# driver_f103__EDA.net
KiCad netlist of a schematic drawn in EasyEDA
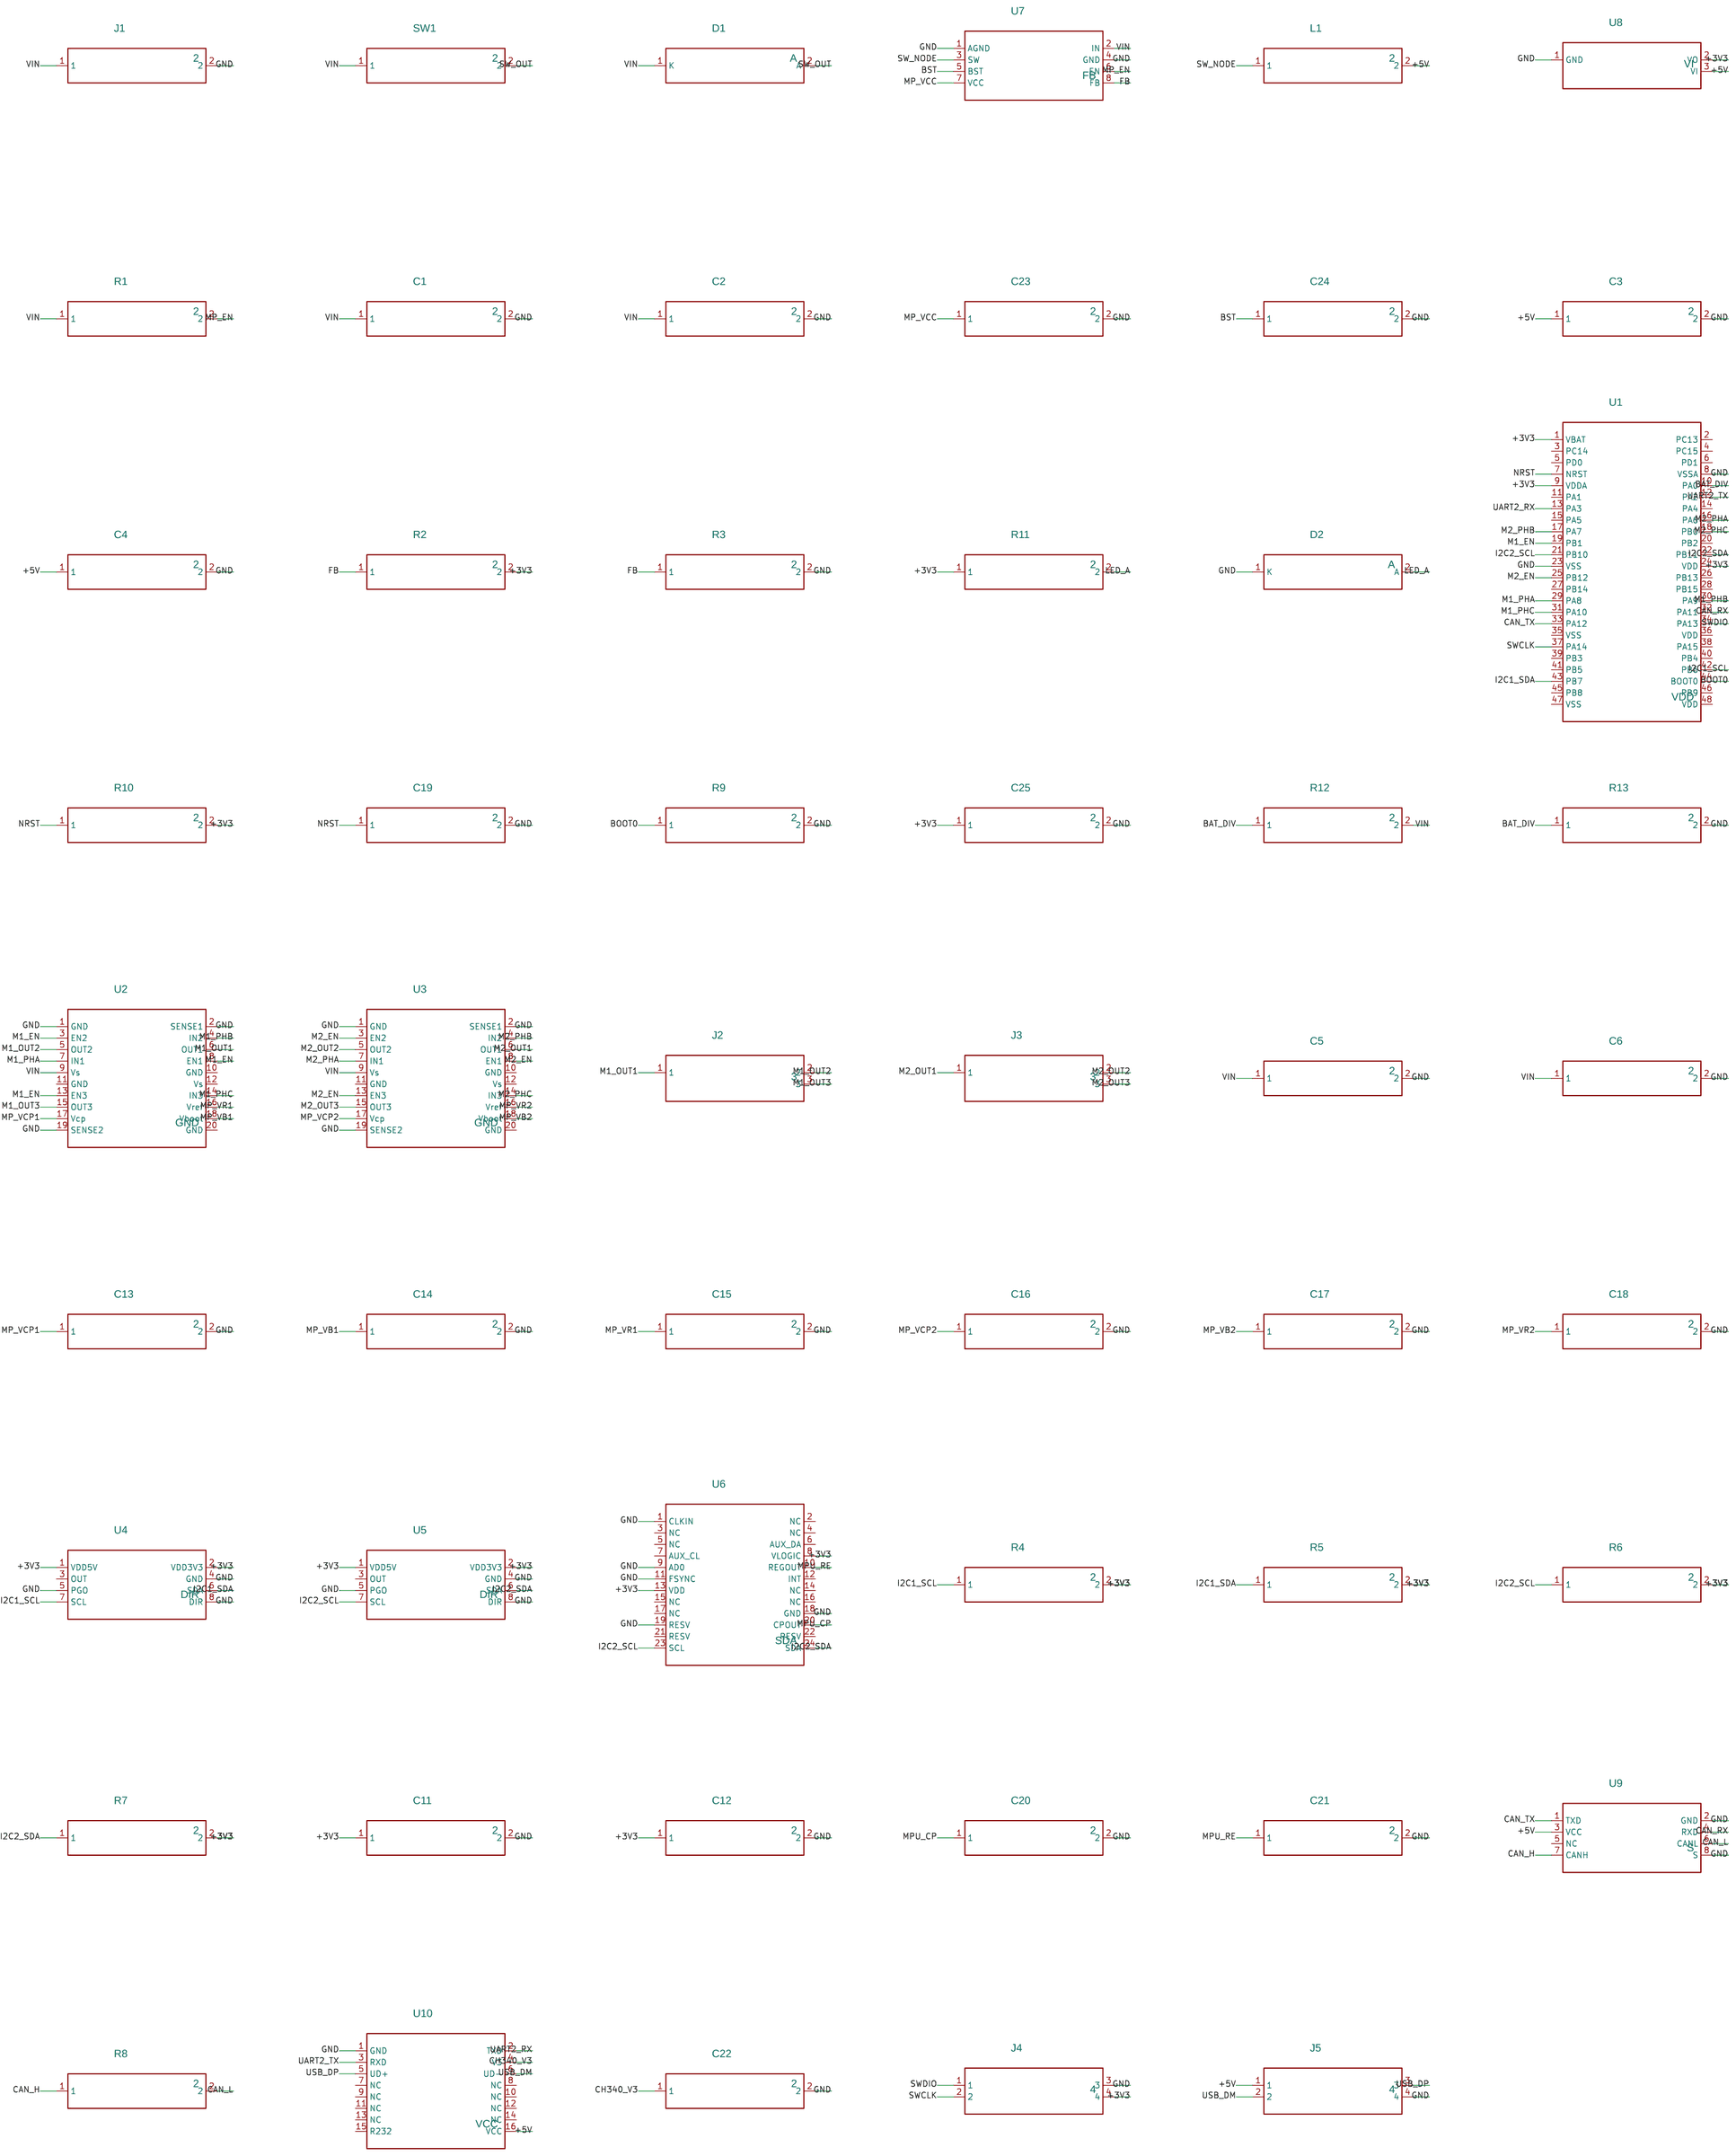
[diagram p0: schematic sheet]

(export (version "E")
  (design (tool "Eeschema 10.0.6"))
  (components
    (comp (ref "C1") (value "22uF") (libsource (lib "") (part "Unknown_560_520")))
    (comp (ref "C2") (value "0.1uF") (libsource (lib "") (part "Unknown_820_520")))
    (comp (ref "C3") (value "22uF") (libsource (lib "") (part "Unknown_1600_520")))
    (comp (ref "C4") (value "0.1uF") (libsource (lib "") (part "Unknown_300_740")))
    (comp (ref "C5") (value "100uF") (libsource (lib "") (part "Unknown_1340_1180")))
    (comp (ref "C6") (value "100nF") (libsource (lib "") (part "Unknown_1600_1180")))
    (comp (ref "C11") (value "100nF") (libsource (lib "") (part "Unknown_560_1840")))
    (comp (ref "C12") (value "100nF") (libsource (lib "") (part "Unknown_820_1840")))
    (comp (ref "C13") (value "220nF") (libsource (lib "") (part "Unknown_300_1400")))
    (comp (ref "C14") (value "1uF") (libsource (lib "") (part "Unknown_560_1400")))
    (comp (ref "C15") (value "10nF") (libsource (lib "") (part "Unknown_820_1400")))
    (comp (ref "C16") (value "220nF") (libsource (lib "") (part "Unknown_1080_1400")))
    (comp (ref "C17") (value "1uF") (libsource (lib "") (part "Unknown_1340_1400")))
    (comp (ref "C18") (value "10nF") (libsource (lib "") (part "Unknown_1600_1400")))
    (comp (ref "C19") (value "100nF") (libsource (lib "") (part "Unknown_560_960")))
    (comp (ref "C20") (value "2.2uF") (libsource (lib "") (part "Unknown_1080_1840")))
    (comp (ref "C21") (value "0.1uF") (libsource (lib "") (part "Unknown_1340_1840")))
    (comp (ref "C22") (value "10nF") (libsource (lib "") (part "Unknown_820_2060")))
    (comp (ref "C23") (value "1uF") (libsource (lib "") (part "Unknown_1080_520")))
    (comp (ref "C24") (value "0.1uF") (libsource (lib "") (part "Unknown_1340_520")))
    (comp (ref "C25") (value "100nF") (libsource (lib "") (part "Unknown_1080_960")))
    (comp (ref "D1") (value "SS34") (libsource (lib "") (part "Unknown_820_300")))
    (comp (ref "D2") (value "RED") (libsource (lib "") (part "Unknown_1340_740")))
    (comp (ref "J1") (value "BAT") (libsource (lib "") (part "Unknown_300_300")))
    (comp (ref "J2") (value "M1") (libsource (lib "") (part "Unknown_820_1180")))
    (comp (ref "J3") (value "M2") (libsource (lib "") (part "Unknown_1080_1180")))
    (comp (ref "J4") (value "SWD") (libsource (lib "") (part "Unknown_1080_2060")))
    (comp (ref "J5") (value "USB") (libsource (lib "") (part "Unknown_1340_2060")))
    (comp (ref "L1") (value "4.7uH") (libsource (lib "") (part "Unknown_1340_300")))
    (comp (ref "R1") (value "100k") (libsource (lib "") (part "Unknown_300_520")))
    (comp (ref "R2") (value "40.2k") (libsource (lib "") (part "Unknown_560_740")))
    (comp (ref "R3") (value "5.49k") (libsource (lib "") (part "Unknown_820_740")))
    (comp (ref "R4") (value "4.7k") (libsource (lib "") (part "Unknown_1080_1620")))
    (comp (ref "R5") (value "4.7k") (libsource (lib "") (part "Unknown_1340_1620")))
    (comp (ref "R6") (value "4.7k") (libsource (lib "") (part "Unknown_1600_1620")))
    (comp (ref "R7") (value "4.7k") (libsource (lib "") (part "Unknown_300_1840")))
    (comp (ref "R8") (value "120") (libsource (lib "") (part "Unknown_300_2060")))
    (comp (ref "R9") (value "10k") (libsource (lib "") (part "Unknown_820_960")))
    (comp (ref "R10") (value "10k") (libsource (lib "") (part "Unknown_300_960")))
    (comp (ref "R11") (value "1k") (libsource (lib "") (part "Unknown_1080_740")))
    (comp (ref "R12") (value "100k") (libsource (lib "") (part "Unknown_1340_960")))
    (comp (ref "R13") (value "100k") (libsource (lib "") (part "Unknown_1600_960")))
    (comp (ref "SW1") (value "SW") (libsource (lib "") (part "Unknown_560_300")))
    (comp (ref "U1") (value "STM32F103C8T6") (libsource (lib "") (part "Unknown_1600_740")))
    (comp (ref "U2") (value "L6234") (libsource (lib "") (part "Unknown_300_1180")))
    (comp (ref "U3") (value "L6234") (libsource (lib "") (part "Unknown_560_1180")))
    (comp (ref "U4") (value "AS5600") (libsource (lib "") (part "Unknown_300_1620")))
    (comp (ref "U5") (value "AS5600") (libsource (lib "") (part "Unknown_560_1620")))
    (comp (ref "U6") (value "MPU6050") (libsource (lib "") (part "Unknown_820_1620")))
    (comp (ref "U7") (value "MP2225") (libsource (lib "") (part "Unknown_1080_300")))
    (comp (ref "U8") (value "AMS1117-3.3") (libsource (lib "") (part "Unknown_1600_300")))
    (comp (ref "U9") (value "TJA1051T") (libsource (lib "") (part "Unknown_1600_1840")))
    (comp (ref "U10") (value "CH340C") (libsource (lib "") (part "Unknown_560_2060")))
  )
  (nets
    (net (code "1") (name "/+3V3") (class "Default")
      (node (ref "C11") (pin "1") (pinfunction "1_1") (pintype "unspecified"))
      (node (ref "C12") (pin "1") (pinfunction "1_1") (pintype "unspecified"))
      (node (ref "C25") (pin "1") (pinfunction "1_1") (pintype "unspecified"))
      (node (ref "J4") (pin "4") (pinfunction "4_4") (pintype "unspecified"))
      (node (ref "R10") (pin "2") (pinfunction "2_2") (pintype "unspecified"))
      (node (ref "R11") (pin "1") (pinfunction "1_1") (pintype "unspecified"))
      (node (ref "R2") (pin "2") (pinfunction "2_2") (pintype "unspecified"))
      (node (ref "R4") (pin "2") (pinfunction "2_2") (pintype "unspecified"))
      (node (ref "R5") (pin "2") (pinfunction "2_2") (pintype "unspecified"))
      (node (ref "R6") (pin "2") (pinfunction "2_2") (pintype "unspecified"))
      (node (ref "R7") (pin "2") (pinfunction "2_2") (pintype "unspecified"))
      (node (ref "U1") (pin "1") (pinfunction "VBAT_1") (pintype "unspecified"))
      (node (ref "U1") (pin "24") (pinfunction "VDD_24") (pintype "unspecified"))
      (node (ref "U1") (pin "9") (pinfunction "VDDA_9") (pintype "unspecified"))
      (node (ref "U4") (pin "1") (pinfunction "VDD5V_1") (pintype "unspecified"))
      (node (ref "U4") (pin "2") (pinfunction "VDD3V3_2") (pintype "unspecified"))
      (node (ref "U5") (pin "1") (pinfunction "VDD5V_1") (pintype "unspecified"))
      (node (ref "U5") (pin "2") (pinfunction "VDD3V3_2") (pintype "unspecified"))
      (node (ref "U6") (pin "13") (pinfunction "VDD_13") (pintype "unspecified"))
      (node (ref "U6") (pin "8") (pinfunction "VLOGIC_8") (pintype "unspecified"))
      (node (ref "U8") (pin "2") (pinfunction "VO_2") (pintype "unspecified"))
    )
    (net (code "2") (name "/+5V") (class "Default")
      (node (ref "C3") (pin "1") (pinfunction "1_1") (pintype "unspecified"))
      (node (ref "C4") (pin "1") (pinfunction "1_1") (pintype "unspecified"))
      (node (ref "J5") (pin "1") (pinfunction "1_1") (pintype "unspecified"))
      (node (ref "L1") (pin "2") (pinfunction "2_2") (pintype "unspecified"))
      (node (ref "U10") (pin "16") (pinfunction "VCC_16") (pintype "unspecified"))
      (node (ref "U8") (pin "3") (pinfunction "VI_3") (pintype "unspecified"))
      (node (ref "U9") (pin "3") (pinfunction "VCC_3") (pintype "unspecified"))
    )
    (net (code "3") (name "/BAT_DIV") (class "Default")
      (node (ref "R12") (pin "1") (pinfunction "1_1") (pintype "unspecified"))
      (node (ref "R13") (pin "1") (pinfunction "1_1") (pintype "unspecified"))
      (node (ref "U1") (pin "10") (pinfunction "PA0_10") (pintype "unspecified"))
    )
    (net (code "4") (name "/BOOT0") (class "Default")
      (node (ref "R9") (pin "1") (pinfunction "1_1") (pintype "unspecified"))
      (node (ref "U1") (pin "44") (pinfunction "BOOT0_44") (pintype "unspecified"))
    )
    (net (code "5") (name "/BST") (class "Default")
      (node (ref "C24") (pin "1") (pinfunction "1_1") (pintype "unspecified"))
      (node (ref "U7") (pin "5") (pinfunction "BST_5") (pintype "unspecified"))
    )
    (net (code "6") (name "/CAN_H") (class "Default")
      (node (ref "R8") (pin "1") (pinfunction "1_1") (pintype "unspecified"))
      (node (ref "U9") (pin "7") (pinfunction "CANH_7") (pintype "unspecified"))
    )
    (net (code "7") (name "/CAN_L") (class "Default")
      (node (ref "R8") (pin "2") (pinfunction "2_2") (pintype "unspecified"))
      (node (ref "U9") (pin "6") (pinfunction "CANL_6") (pintype "unspecified"))
    )
    (net (code "8") (name "/CAN_RX") (class "Default")
      (node (ref "U1") (pin "32") (pinfunction "PA11_32") (pintype "unspecified"))
      (node (ref "U9") (pin "4") (pinfunction "RXD_4") (pintype "unspecified"))
    )
    (net (code "9") (name "/CAN_TX") (class "Default")
      (node (ref "U1") (pin "33") (pinfunction "PA12_33") (pintype "unspecified"))
      (node (ref "U9") (pin "1") (pinfunction "TXD_1") (pintype "unspecified"))
    )
    (net (code "10") (name "/CH340_V3") (class "Default")
      (node (ref "C22") (pin "1") (pinfunction "1_1") (pintype "unspecified"))
      (node (ref "U10") (pin "4") (pinfunction "V3_4") (pintype "unspecified"))
    )
    (net (code "11") (name "/FB") (class "Default")
      (node (ref "R2") (pin "1") (pinfunction "1_1") (pintype "unspecified"))
      (node (ref "R3") (pin "1") (pinfunction "1_1") (pintype "unspecified"))
      (node (ref "U7") (pin "8") (pinfunction "FB_8") (pintype "unspecified"))
    )
    (net (code "12") (name "/GND") (class "Default")
      (node (ref "C1") (pin "2") (pinfunction "2_2") (pintype "unspecified"))
      (node (ref "C11") (pin "2") (pinfunction "2_2") (pintype "unspecified"))
      (node (ref "C12") (pin "2") (pinfunction "2_2") (pintype "unspecified"))
      (node (ref "C13") (pin "2") (pinfunction "2_2") (pintype "unspecified"))
      (node (ref "C14") (pin "2") (pinfunction "2_2") (pintype "unspecified"))
      (node (ref "C15") (pin "2") (pinfunction "2_2") (pintype "unspecified"))
      (node (ref "C16") (pin "2") (pinfunction "2_2") (pintype "unspecified"))
      (node (ref "C17") (pin "2") (pinfunction "2_2") (pintype "unspecified"))
      (node (ref "C18") (pin "2") (pinfunction "2_2") (pintype "unspecified"))
      (node (ref "C19") (pin "2") (pinfunction "2_2") (pintype "unspecified"))
      (node (ref "C2") (pin "2") (pinfunction "2_2") (pintype "unspecified"))
      (node (ref "C20") (pin "2") (pinfunction "2_2") (pintype "unspecified"))
      (node (ref "C21") (pin "2") (pinfunction "2_2") (pintype "unspecified"))
      (node (ref "C22") (pin "2") (pinfunction "2_2") (pintype "unspecified"))
      (node (ref "C23") (pin "2") (pinfunction "2_2") (pintype "unspecified"))
      (node (ref "C24") (pin "2") (pinfunction "2_2") (pintype "unspecified"))
      (node (ref "C25") (pin "2") (pinfunction "2_2") (pintype "unspecified"))
      (node (ref "C3") (pin "2") (pinfunction "2_2") (pintype "unspecified"))
      (node (ref "C4") (pin "2") (pinfunction "2_2") (pintype "unspecified"))
      (node (ref "C5") (pin "2") (pinfunction "2_2") (pintype "unspecified"))
      (node (ref "C6") (pin "2") (pinfunction "2_2") (pintype "unspecified"))
      (node (ref "D2") (pin "1") (pinfunction "K_1") (pintype "unspecified"))
      (node (ref "J1") (pin "2") (pinfunction "2_2") (pintype "unspecified"))
      (node (ref "J4") (pin "3") (pinfunction "3_3") (pintype "unspecified"))
      (node (ref "J5") (pin "4") (pinfunction "4_4") (pintype "unspecified"))
      (node (ref "R13") (pin "2") (pinfunction "2_2") (pintype "unspecified"))
      (node (ref "R3") (pin "2") (pinfunction "2_2") (pintype "unspecified"))
      (node (ref "R9") (pin "2") (pinfunction "2_2") (pintype "unspecified"))
      (node (ref "U1") (pin "23") (pinfunction "VSS_23") (pintype "unspecified"))
      (node (ref "U1") (pin "8") (pinfunction "VSSA_8") (pintype "unspecified"))
      (node (ref "U10") (pin "1") (pinfunction "GND_1") (pintype "unspecified"))
      (node (ref "U2") (pin "1") (pinfunction "GND_1") (pintype "unspecified"))
      (node (ref "U2") (pin "19") (pinfunction "SENSE2_19") (pintype "unspecified"))
      (node (ref "U2") (pin "2") (pinfunction "SENSE1_2") (pintype "unspecified"))
      (node (ref "U3") (pin "1") (pinfunction "GND_1") (pintype "unspecified"))
      (node (ref "U3") (pin "19") (pinfunction "SENSE2_19") (pintype "unspecified"))
      (node (ref "U3") (pin "2") (pinfunction "SENSE1_2") (pintype "unspecified"))
      (node (ref "U4") (pin "4") (pinfunction "GND_4") (pintype "unspecified"))
      (node (ref "U4") (pin "5") (pinfunction "PGO_5") (pintype "unspecified"))
      (node (ref "U4") (pin "8") (pinfunction "DIR_8") (pintype "unspecified"))
      (node (ref "U5") (pin "4") (pinfunction "GND_4") (pintype "unspecified"))
      (node (ref "U5") (pin "5") (pinfunction "PGO_5") (pintype "unspecified"))
      (node (ref "U5") (pin "8") (pinfunction "DIR_8") (pintype "unspecified"))
      (node (ref "U6") (pin "1") (pinfunction "CLKIN_1") (pintype "unspecified"))
      (node (ref "U6") (pin "11") (pinfunction "FSYNC_11") (pintype "unspecified"))
      (node (ref "U6") (pin "18") (pinfunction "GND_18") (pintype "unspecified"))
      (node (ref "U6") (pin "19") (pinfunction "RESV_19") (pintype "unspecified"))
      (node (ref "U6") (pin "9") (pinfunction "AD0_9") (pintype "unspecified"))
      (node (ref "U7") (pin "1") (pinfunction "AGND_1") (pintype "unspecified"))
      (node (ref "U7") (pin "4") (pinfunction "GND_4") (pintype "unspecified"))
      (node (ref "U8") (pin "1") (pinfunction "GND_1") (pintype "unspecified"))
      (node (ref "U9") (pin "2") (pinfunction "GND_2") (pintype "unspecified"))
      (node (ref "U9") (pin "8") (pinfunction "S_8") (pintype "unspecified"))
    )
    (net (code "13") (name "/I2C1_SCL") (class "Default")
      (node (ref "R4") (pin "1") (pinfunction "1_1") (pintype "unspecified"))
      (node (ref "U1") (pin "42") (pinfunction "PB6_42") (pintype "unspecified"))
      (node (ref "U4") (pin "7") (pinfunction "SCL_7") (pintype "unspecified"))
    )
    (net (code "14") (name "/I2C1_SDA") (class "Default")
      (node (ref "R5") (pin "1") (pinfunction "1_1") (pintype "unspecified"))
      (node (ref "U1") (pin "43") (pinfunction "PB7_43") (pintype "unspecified"))
      (node (ref "U4") (pin "6") (pinfunction "SDA_6") (pintype "unspecified"))
    )
    (net (code "15") (name "/I2C2_SCL") (class "Default")
      (node (ref "R6") (pin "1") (pinfunction "1_1") (pintype "unspecified"))
      (node (ref "U1") (pin "21") (pinfunction "PB10_21") (pintype "unspecified"))
      (node (ref "U5") (pin "7") (pinfunction "SCL_7") (pintype "unspecified"))
      (node (ref "U6") (pin "23") (pinfunction "SCL_23") (pintype "unspecified"))
    )
    (net (code "16") (name "/I2C2_SDA") (class "Default")
      (node (ref "R7") (pin "1") (pinfunction "1_1") (pintype "unspecified"))
      (node (ref "U1") (pin "22") (pinfunction "PB11_22") (pintype "unspecified"))
      (node (ref "U5") (pin "6") (pinfunction "SDA_6") (pintype "unspecified"))
      (node (ref "U6") (pin "24") (pinfunction "SDA_24") (pintype "unspecified"))
    )
    (net (code "17") (name "/LED_A") (class "Default")
      (node (ref "D2") (pin "2") (pinfunction "A_2") (pintype "unspecified"))
      (node (ref "R11") (pin "2") (pinfunction "2_2") (pintype "unspecified"))
    )
    (net (code "18") (name "/M1_EN") (class "Default")
      (node (ref "U1") (pin "19") (pinfunction "PB1_19") (pintype "unspecified"))
      (node (ref "U2") (pin "13") (pinfunction "EN3_13") (pintype "unspecified"))
      (node (ref "U2") (pin "3") (pinfunction "EN2_3") (pintype "unspecified"))
      (node (ref "U2") (pin "8") (pinfunction "EN1_8") (pintype "unspecified"))
    )
    (net (code "19") (name "/M1_OUT1") (class "Default")
      (node (ref "J2") (pin "1") (pinfunction "1_1") (pintype "unspecified"))
      (node (ref "U2") (pin "6") (pinfunction "OUT1_6") (pintype "unspecified"))
    )
    (net (code "20") (name "/M1_OUT2") (class "Default")
      (node (ref "J2") (pin "2") (pinfunction "2_2") (pintype "unspecified"))
      (node (ref "U2") (pin "5") (pinfunction "OUT2_5") (pintype "unspecified"))
    )
    (net (code "21") (name "/M1_OUT3") (class "Default")
      (node (ref "J2") (pin "3") (pinfunction "3_3") (pintype "unspecified"))
      (node (ref "U2") (pin "15") (pinfunction "OUT3_15") (pintype "unspecified"))
    )
    (net (code "22") (name "/M1_PHA") (class "Default")
      (node (ref "U1") (pin "29") (pinfunction "PA8_29") (pintype "unspecified"))
      (node (ref "U2") (pin "7") (pinfunction "IN1_7") (pintype "unspecified"))
    )
    (net (code "23") (name "/M1_PHB") (class "Default")
      (node (ref "U1") (pin "30") (pinfunction "PA9_30") (pintype "unspecified"))
      (node (ref "U2") (pin "4") (pinfunction "IN2_4") (pintype "unspecified"))
    )
    (net (code "24") (name "/M1_PHC") (class "Default")
      (node (ref "U1") (pin "31") (pinfunction "PA10_31") (pintype "unspecified"))
      (node (ref "U2") (pin "14") (pinfunction "IN3_14") (pintype "unspecified"))
    )
    (net (code "25") (name "/M2_EN") (class "Default")
      (node (ref "U1") (pin "25") (pinfunction "PB12_25") (pintype "unspecified"))
      (node (ref "U3") (pin "13") (pinfunction "EN3_13") (pintype "unspecified"))
      (node (ref "U3") (pin "3") (pinfunction "EN2_3") (pintype "unspecified"))
      (node (ref "U3") (pin "8") (pinfunction "EN1_8") (pintype "unspecified"))
    )
    (net (code "26") (name "/M2_OUT1") (class "Default")
      (node (ref "J3") (pin "1") (pinfunction "1_1") (pintype "unspecified"))
      (node (ref "U3") (pin "6") (pinfunction "OUT1_6") (pintype "unspecified"))
    )
    (net (code "27") (name "/M2_OUT2") (class "Default")
      (node (ref "J3") (pin "2") (pinfunction "2_2") (pintype "unspecified"))
      (node (ref "U3") (pin "5") (pinfunction "OUT2_5") (pintype "unspecified"))
    )
    (net (code "28") (name "/M2_OUT3") (class "Default")
      (node (ref "J3") (pin "3") (pinfunction "3_3") (pintype "unspecified"))
      (node (ref "U3") (pin "15") (pinfunction "OUT3_15") (pintype "unspecified"))
    )
    (net (code "29") (name "/M2_PHA") (class "Default")
      (node (ref "U1") (pin "16") (pinfunction "PA6_16") (pintype "unspecified"))
      (node (ref "U3") (pin "7") (pinfunction "IN1_7") (pintype "unspecified"))
    )
    (net (code "30") (name "/M2_PHB") (class "Default")
      (node (ref "U1") (pin "17") (pinfunction "PA7_17") (pintype "unspecified"))
      (node (ref "U3") (pin "4") (pinfunction "IN2_4") (pintype "unspecified"))
    )
    (net (code "31") (name "/M2_PHC") (class "Default")
      (node (ref "U1") (pin "18") (pinfunction "PB0_18") (pintype "unspecified"))
      (node (ref "U3") (pin "14") (pinfunction "IN3_14") (pintype "unspecified"))
    )
    (net (code "32") (name "/MPU_CP") (class "Default")
      (node (ref "C20") (pin "1") (pinfunction "1_1") (pintype "unspecified"))
      (node (ref "U6") (pin "20") (pinfunction "CPOUT_20") (pintype "unspecified"))
    )
    (net (code "33") (name "/MPU_RE") (class "Default")
      (node (ref "C21") (pin "1") (pinfunction "1_1") (pintype "unspecified"))
      (node (ref "U6") (pin "10") (pinfunction "REGOUT_10") (pintype "unspecified"))
    )
    (net (code "34") (name "/MP_EN") (class "Default")
      (node (ref "R1") (pin "2") (pinfunction "2_2") (pintype "unspecified"))
      (node (ref "U7") (pin "6") (pinfunction "EN_6") (pintype "unspecified"))
    )
    (net (code "35") (name "/MP_VB1") (class "Default")
      (node (ref "C14") (pin "1") (pinfunction "1_1") (pintype "unspecified"))
      (node (ref "U2") (pin "18") (pinfunction "Vboot_18") (pintype "unspecified"))
    )
    (net (code "36") (name "/MP_VB2") (class "Default")
      (node (ref "C17") (pin "1") (pinfunction "1_1") (pintype "unspecified"))
      (node (ref "U3") (pin "18") (pinfunction "Vboot_18") (pintype "unspecified"))
    )
    (net (code "37") (name "/MP_VCC") (class "Default")
      (node (ref "C23") (pin "1") (pinfunction "1_1") (pintype "unspecified"))
      (node (ref "U7") (pin "7") (pinfunction "VCC_7") (pintype "unspecified"))
    )
    (net (code "38") (name "/MP_VCP1") (class "Default")
      (node (ref "C13") (pin "1") (pinfunction "1_1") (pintype "unspecified"))
      (node (ref "U2") (pin "17") (pinfunction "Vcp_17") (pintype "unspecified"))
    )
    (net (code "39") (name "/MP_VCP2") (class "Default")
      (node (ref "C16") (pin "1") (pinfunction "1_1") (pintype "unspecified"))
      (node (ref "U3") (pin "17") (pinfunction "Vcp_17") (pintype "unspecified"))
    )
    (net (code "40") (name "/MP_VR1") (class "Default")
      (node (ref "C15") (pin "1") (pinfunction "1_1") (pintype "unspecified"))
      (node (ref "U2") (pin "16") (pinfunction "Vref_16") (pintype "unspecified"))
    )
    (net (code "41") (name "/MP_VR2") (class "Default")
      (node (ref "C18") (pin "1") (pinfunction "1_1") (pintype "unspecified"))
      (node (ref "U3") (pin "16") (pinfunction "Vref_16") (pintype "unspecified"))
    )
    (net (code "42") (name "/NRST") (class "Default")
      (node (ref "C19") (pin "1") (pinfunction "1_1") (pintype "unspecified"))
      (node (ref "R10") (pin "1") (pinfunction "1_1") (pintype "unspecified"))
      (node (ref "U1") (pin "7") (pinfunction "NRST_7") (pintype "unspecified"))
    )
    (net (code "43") (name "/SWCLK") (class "Default")
      (node (ref "J4") (pin "2") (pinfunction "2_2") (pintype "unspecified"))
      (node (ref "U1") (pin "37") (pinfunction "PA14_37") (pintype "unspecified"))
    )
    (net (code "44") (name "/SWDIO") (class "Default")
      (node (ref "J4") (pin "1") (pinfunction "1_1") (pintype "unspecified"))
      (node (ref "U1") (pin "34") (pinfunction "PA13_34") (pintype "unspecified"))
    )
    (net (code "45") (name "/SW_NODE") (class "Default")
      (node (ref "L1") (pin "1") (pinfunction "1_1") (pintype "unspecified"))
      (node (ref "U7") (pin "3") (pinfunction "SW_3") (pintype "unspecified"))
    )
    (net (code "46") (name "/SW_OUT") (class "Default")
      (node (ref "D1") (pin "2") (pinfunction "A_2") (pintype "unspecified"))
      (node (ref "SW1") (pin "2") (pinfunction "2_2") (pintype "unspecified"))
    )
    (net (code "47") (name "/UART2_RX") (class "Default")
      (node (ref "U1") (pin "13") (pinfunction "PA3_13") (pintype "unspecified"))
      (node (ref "U10") (pin "2") (pinfunction "TXD_2") (pintype "unspecified"))
    )
    (net (code "48") (name "/UART2_TX") (class "Default")
      (node (ref "U1") (pin "12") (pinfunction "PA2_12") (pintype "unspecified"))
      (node (ref "U10") (pin "3") (pinfunction "RXD_3") (pintype "unspecified"))
    )
    (net (code "49") (name "/USB_DM") (class "Default")
      (node (ref "J5") (pin "2") (pinfunction "2_2") (pintype "unspecified"))
      (node (ref "U10") (pin "6") (pinfunction "UD-_6") (pintype "unspecified"))
    )
    (net (code "50") (name "/USB_DP") (class "Default")
      (node (ref "J5") (pin "3") (pinfunction "3_3") (pintype "unspecified"))
      (node (ref "U10") (pin "5") (pinfunction "UD+_5") (pintype "unspecified"))
    )
    (net (code "51") (name "/VIN") (class "Default")
      (node (ref "C1") (pin "1") (pinfunction "1_1") (pintype "unspecified"))
      (node (ref "C2") (pin "1") (pinfunction "1_1") (pintype "unspecified"))
      (node (ref "C5") (pin "1") (pinfunction "1_1") (pintype "unspecified"))
      (node (ref "C6") (pin "1") (pinfunction "1_1") (pintype "unspecified"))
      (node (ref "D1") (pin "1") (pinfunction "K_1") (pintype "unspecified"))
      (node (ref "J1") (pin "1") (pinfunction "1_1") (pintype "unspecified"))
      (node (ref "R1") (pin "1") (pinfunction "1_1") (pintype "unspecified"))
      (node (ref "R12") (pin "2") (pinfunction "2_2") (pintype "unspecified"))
      (node (ref "SW1") (pin "1") (pinfunction "1_1") (pintype "unspecified"))
      (node (ref "U2") (pin "9") (pinfunction "Vs_9") (pintype "unspecified"))
      (node (ref "U3") (pin "9") (pinfunction "Vs_9") (pintype "unspecified"))
      (node (ref "U7") (pin "2") (pinfunction "IN_2") (pintype "unspecified"))
    )
    (net (code "52") (name "unconnected-(U1-PA1-Pad11)") (class "Default")
      (node (ref "U1") (pin "11") (pinfunction "PA1_11") (pintype "unspecified"))
    )
    (net (code "53") (name "unconnected-(U1-PA4-Pad14)") (class "Default")
      (node (ref "U1") (pin "14") (pinfunction "PA4_14") (pintype "unspecified"))
    )
    (net (code "54") (name "unconnected-(U1-PA5-Pad15)") (class "Default")
      (node (ref "U1") (pin "15") (pinfunction "PA5_15") (pintype "unspecified"))
    )
    (net (code "55") (name "unconnected-(U1-PA15-Pad38)") (class "Default")
      (node (ref "U1") (pin "38") (pinfunction "PA15_38") (pintype "unspecified"))
    )
    (net (code "56") (name "unconnected-(U1-PB2-Pad20)") (class "Default")
      (node (ref "U1") (pin "20") (pinfunction "PB2_20") (pintype "unspecified"))
    )
    (net (code "57") (name "unconnected-(U1-PB3-Pad39)") (class "Default")
      (node (ref "U1") (pin "39") (pinfunction "PB3_39") (pintype "unspecified"))
    )
    (net (code "58") (name "unconnected-(U1-PB4-Pad40)") (class "Default")
      (node (ref "U1") (pin "40") (pinfunction "PB4_40") (pintype "unspecified"))
    )
    (net (code "59") (name "unconnected-(U1-PB5-Pad41)") (class "Default")
      (node (ref "U1") (pin "41") (pinfunction "PB5_41") (pintype "unspecified"))
    )
    (net (code "60") (name "unconnected-(U1-PB8-Pad45)") (class "Default")
      (node (ref "U1") (pin "45") (pinfunction "PB8_45") (pintype "unspecified"))
    )
    (net (code "61") (name "unconnected-(U1-PB9-Pad46)") (class "Default")
      (node (ref "U1") (pin "46") (pinfunction "PB9_46") (pintype "unspecified"))
    )
    (net (code "62") (name "unconnected-(U1-PB13-Pad26)") (class "Default")
      (node (ref "U1") (pin "26") (pinfunction "PB13_26") (pintype "unspecified"))
    )
    (net (code "63") (name "unconnected-(U1-PB14-Pad27)") (class "Default")
      (node (ref "U1") (pin "27") (pinfunction "PB14_27") (pintype "unspecified"))
    )
    (net (code "64") (name "unconnected-(U1-PB15-Pad28)") (class "Default")
      (node (ref "U1") (pin "28") (pinfunction "PB15_28") (pintype "unspecified"))
    )
    (net (code "65") (name "unconnected-(U1-PC13-Pad2)") (class "Default")
      (node (ref "U1") (pin "2") (pinfunction "PC13_2") (pintype "unspecified"))
    )
    (net (code "66") (name "unconnected-(U1-PC14-Pad3)") (class "Default")
      (node (ref "U1") (pin "3") (pinfunction "PC14_3") (pintype "unspecified"))
    )
    (net (code "67") (name "unconnected-(U1-PC15-Pad4)") (class "Default")
      (node (ref "U1") (pin "4") (pinfunction "PC15_4") (pintype "unspecified"))
    )
    (net (code "68") (name "unconnected-(U1-PD0-Pad5)") (class "Default")
      (node (ref "U1") (pin "5") (pinfunction "PD0_5") (pintype "unspecified"))
    )
    (net (code "69") (name "unconnected-(U1-PD1-Pad6)") (class "Default")
      (node (ref "U1") (pin "6") (pinfunction "PD1_6") (pintype "unspecified"))
    )
    (net (code "70") (name "unconnected-(U1-VDD-Pad36)") (class "Default")
      (node (ref "U1") (pin "36") (pinfunction "VDD_36") (pintype "unspecified"))
    )
    (net (code "71") (name "unconnected-(U1-VDD-Pad48)") (class "Default")
      (node (ref "U1") (pin "48") (pinfunction "VDD_48") (pintype "unspecified"))
    )
    (net (code "72") (name "unconnected-(U1-VSS-Pad35)") (class "Default")
      (node (ref "U1") (pin "35") (pinfunction "VSS_35") (pintype "unspecified"))
    )
    (net (code "73") (name "unconnected-(U1-VSS-Pad47)") (class "Default")
      (node (ref "U1") (pin "47") (pinfunction "VSS_47") (pintype "unspecified"))
    )
    (net (code "74") (name "unconnected-(U2-GND-Pad10)") (class "Default")
      (node (ref "U2") (pin "10") (pinfunction "GND_10") (pintype "unspecified"))
    )
    (net (code "75") (name "unconnected-(U2-GND-Pad11)") (class "Default")
      (node (ref "U2") (pin "11") (pinfunction "GND_11") (pintype "unspecified"))
    )
    (net (code "76") (name "unconnected-(U2-GND-Pad20)") (class "Default")
      (node (ref "U2") (pin "20") (pinfunction "GND_20") (pintype "unspecified"))
    )
    (net (code "77") (name "unconnected-(U2-Vs-Pad12)") (class "Default")
      (node (ref "U2") (pin "12") (pinfunction "Vs_12") (pintype "unspecified"))
    )
    (net (code "78") (name "unconnected-(U3-GND-Pad10)") (class "Default")
      (node (ref "U3") (pin "10") (pinfunction "GND_10") (pintype "unspecified"))
    )
    (net (code "79") (name "unconnected-(U3-GND-Pad11)") (class "Default")
      (node (ref "U3") (pin "11") (pinfunction "GND_11") (pintype "unspecified"))
    )
    (net (code "80") (name "unconnected-(U3-GND-Pad20)") (class "Default")
      (node (ref "U3") (pin "20") (pinfunction "GND_20") (pintype "unspecified"))
    )
    (net (code "81") (name "unconnected-(U3-Vs-Pad12)") (class "Default")
      (node (ref "U3") (pin "12") (pinfunction "Vs_12") (pintype "unspecified"))
    )
    (net (code "82") (name "unconnected-(U4-OUT-Pad3)") (class "Default")
      (node (ref "U4") (pin "3") (pinfunction "OUT_3") (pintype "unspecified"))
    )
    (net (code "83") (name "unconnected-(U5-OUT-Pad3)") (class "Default")
      (node (ref "U5") (pin "3") (pinfunction "OUT_3") (pintype "unspecified"))
    )
    (net (code "84") (name "unconnected-(U6-AUX_CL-Pad7)") (class "Default")
      (node (ref "U6") (pin "7") (pinfunction "AUX_CL_7") (pintype "unspecified"))
    )
    (net (code "85") (name "unconnected-(U6-AUX_DA-Pad6)") (class "Default")
      (node (ref "U6") (pin "6") (pinfunction "AUX_DA_6") (pintype "unspecified"))
    )
    (net (code "86") (name "unconnected-(U6-INT-Pad12)") (class "Default")
      (node (ref "U6") (pin "12") (pinfunction "INT_12") (pintype "unspecified"))
    )
    (net (code "87") (name "unconnected-(U6-NC-Pad2)") (class "Default")
      (node (ref "U6") (pin "2") (pinfunction "NC_2") (pintype "unspecified"))
    )
    (net (code "88") (name "unconnected-(U6-NC-Pad3)") (class "Default")
      (node (ref "U6") (pin "3") (pinfunction "NC_3") (pintype "unspecified"))
    )
    (net (code "89") (name "unconnected-(U6-NC-Pad4)") (class "Default")
      (node (ref "U6") (pin "4") (pinfunction "NC_4") (pintype "unspecified"))
    )
    (net (code "90") (name "unconnected-(U6-NC-Pad5)") (class "Default")
      (node (ref "U6") (pin "5") (pinfunction "NC_5") (pintype "unspecified"))
    )
    (net (code "91") (name "unconnected-(U6-NC-Pad14)") (class "Default")
      (node (ref "U6") (pin "14") (pinfunction "NC_14") (pintype "unspecified"))
    )
    (net (code "92") (name "unconnected-(U6-NC-Pad15)") (class "Default")
      (node (ref "U6") (pin "15") (pinfunction "NC_15") (pintype "unspecified"))
    )
    (net (code "93") (name "unconnected-(U6-NC-Pad16)") (class "Default")
      (node (ref "U6") (pin "16") (pinfunction "NC_16") (pintype "unspecified"))
    )
    (net (code "94") (name "unconnected-(U6-NC-Pad17)") (class "Default")
      (node (ref "U6") (pin "17") (pinfunction "NC_17") (pintype "unspecified"))
    )
    (net (code "95") (name "unconnected-(U6-RESV-Pad21)") (class "Default")
      (node (ref "U6") (pin "21") (pinfunction "RESV_21") (pintype "unspecified"))
    )
    (net (code "96") (name "unconnected-(U6-RESV-Pad22)") (class "Default")
      (node (ref "U6") (pin "22") (pinfunction "RESV_22") (pintype "unspecified"))
    )
    (net (code "97") (name "unconnected-(U9-NC-Pad5)") (class "Default")
      (node (ref "U9") (pin "5") (pinfunction "NC_5") (pintype "unspecified"))
    )
    (net (code "98") (name "unconnected-(U10-NC-Pad7)") (class "Default")
      (node (ref "U10") (pin "7") (pinfunction "NC_7") (pintype "unspecified"))
    )
    (net (code "99") (name "unconnected-(U10-NC-Pad8)") (class "Default")
      (node (ref "U10") (pin "8") (pinfunction "NC_8") (pintype "unspecified"))
    )
    (net (code "100") (name "unconnected-(U10-NC-Pad9)") (class "Default")
      (node (ref "U10") (pin "9") (pinfunction "NC_9") (pintype "unspecified"))
    )
    (net (code "101") (name "unconnected-(U10-NC-Pad10)") (class "Default")
      (node (ref "U10") (pin "10") (pinfunction "NC_10") (pintype "unspecified"))
    )
    (net (code "102") (name "unconnected-(U10-NC-Pad11)") (class "Default")
      (node (ref "U10") (pin "11") (pinfunction "NC_11") (pintype "unspecified"))
    )
    (net (code "103") (name "unconnected-(U10-NC-Pad12)") (class "Default")
      (node (ref "U10") (pin "12") (pinfunction "NC_12") (pintype "unspecified"))
    )
    (net (code "104") (name "unconnected-(U10-NC-Pad13)") (class "Default")
      (node (ref "U10") (pin "13") (pinfunction "NC_13") (pintype "unspecified"))
    )
    (net (code "105") (name "unconnected-(U10-NC-Pad14)") (class "Default")
      (node (ref "U10") (pin "14") (pinfunction "NC_14") (pintype "unspecified"))
    )
    (net (code "106") (name "unconnected-(U10-R232-Pad15)") (class "Default")
      (node (ref "U10") (pin "15") (pinfunction "R232_15") (pintype "unspecified"))
    )
  )
)
